# drvamap.net
KiCad netlist of a schematic drawn in Altium Designer
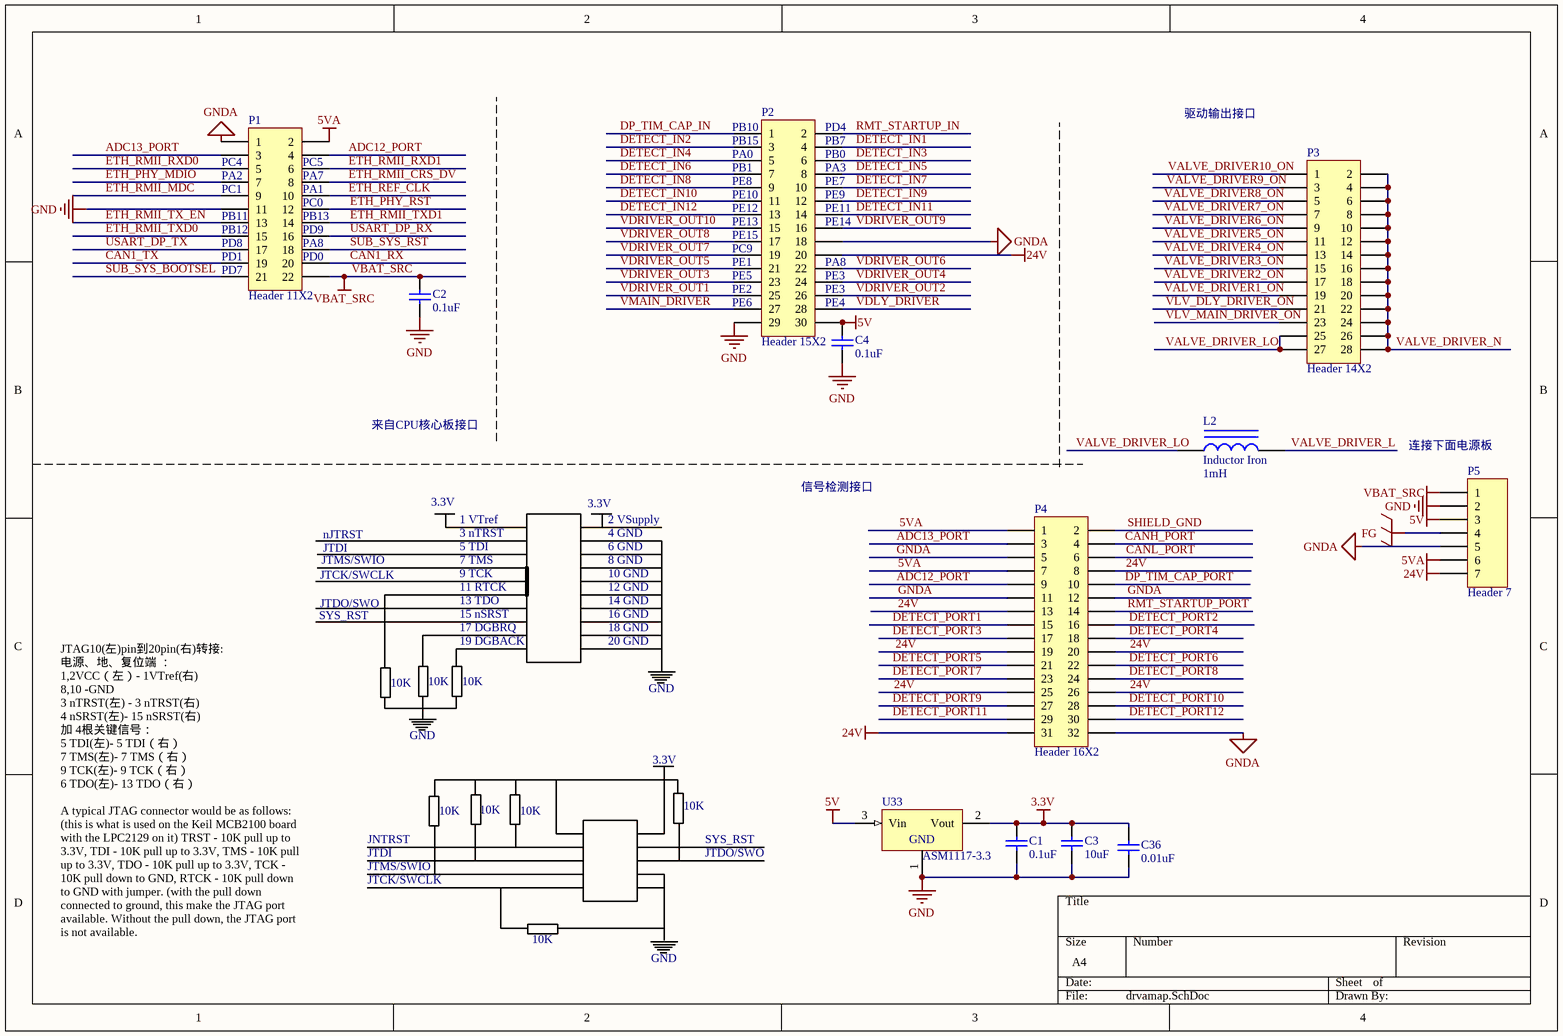
[diagram p0: drvamap.SchDoc]

(export (version "E")
  (design (tool "Eeschema 10.0.6"))
  (components
    (comp (ref "C1")
      (value "0.1uF")
      (footprint "CAPC2012M")
      (description "Capacitor")
      (fields (field (name "PUBLISHER") "Altium Limited"))
      (libsource (lib "Miscellaneous Devices") (part "Cap"))
    )
    (comp (ref "C2")
      (value "0.1uF")
      (footprint "CAPC2012M")
      (description "Capacitor")
      (fields (field (name "PUBLISHER") "Altium Limited"))
      (libsource (lib "Miscellaneous Devices") (part "Cap"))
    )
    (comp (ref "C3")
      (value "10uF")
      (footprint "CAPC2012M")
      (description "Capacitor")
      (fields (field (name "PUBLISHER") "Altium Limited"))
      (libsource (lib "Miscellaneous Devices") (part "Cap"))
    )
    (comp (ref "C4")
      (value "0.1uF")
      (footprint "CAPC2012M")
      (description "Capacitor")
      (fields (field (name "PUBLISHER") "Altium Limited"))
      (libsource (lib "Miscellaneous Devices") (part "Cap"))
    )
    (comp (ref "C36")
      (value "0.01uF")
      (footprint "CAPC2012M")
      (description "Capacitor")
      (fields (field (name "PUBLISHER") "Altium Limited"))
      (libsource (lib "Miscellaneous Devices") (part "Cap"))
    )
    (comp (ref "L2")
      (value "Inductor Iron")
      (footprint "CAPPR5-8x8A")
      (description "Magnetic-Core Inductor")
      (fields (field (name "ALTIUM_VALUE") "1mH") (field (name "PUBLISHER") "Altium Limited"))
      (libsource (lib "Miscellaneous Devices") (part "Inductor Iron"))
    )
    (comp (ref "P1")
      (value "Header 11X2")
      (footprint "HDR2X11")
      (description "Header, 11-Pin, Dual row")
      (fields (field (name "PUBLISHER") "Altium Limited"))
      (libsource (lib "UserSchCon") (part "Header 11X2"))
    )
    (comp (ref "P2")
      (value "Header 15X2")
      (footprint "HDR2X15")
      (description "Header, 15-Pin, Dual row")
      (fields (field (name "PUBLISHER") "Altium Limited"))
      (libsource (lib "UserSchCon") (part "Header 15X2"))
    )
    (comp (ref "P3")
      (value "Header 14X2")
      (footprint "DG127A-3.81-14")
      (description "Header, 14-Pin, Dual row")
      (fields (field (name "PUBLISHER") "Altium Limited"))
      (libsource (lib "UserSchCon") (part "Header 14X2"))
    )
    (comp (ref "P4")
      (value "Header 16X2")
      (footprint "DG127A-3.81-16")
      (description "Header, 16-Pin, Dual row")
      (fields (field (name "PUBLISHER") "Altium Limited"))
      (libsource (lib "UserSchCon") (part "Header 16X2"))
    )
    (comp (ref "P5")
      (value "Header 7")
      (footprint "HDR1X7")
      (description "Header, 7-Pin")
      (fields (field (name "PUBLISHER") "Altium Limited"))
      (libsource (lib "UserSchCon") (part "Header 7"))
    )
    (comp (ref "U33")
      (value "ASM1117-3.3")
      (footprint "SOT-223")
      (description "800mA Low-Dropout Linear Regulator")
      (libsource (lib "UserLib") (part "LM1117T-5.0"))
    )
  )
  (nets
    (net (code "1") (name "/ADC12_PORT") (class "Default")
      (node (ref "P1") (pin "4") (pinfunction "4_4") (pintype "passive"))
      (node (ref "P4") (pin "9") (pinfunction "9_9") (pintype "passive"))
    )
    (net (code "2") (name "/ADC13_PORT") (class "Default")
      (node (ref "P1") (pin "3") (pinfunction "3_3") (pintype "passive"))
      (node (ref "P4") (pin "3") (pinfunction "3_3") (pintype "passive"))
    )
    (net (code "3") (name "/CAN1_RX") (class "Default")
      (node (ref "P1") (pin "20") (pinfunction "20_20") (pintype "passive"))
    )
    (net (code "4") (name "/CAN1_TX") (class "Default")
      (node (ref "P1") (pin "19") (pinfunction "19_19") (pintype "passive"))
    )
    (net (code "5") (name "/CANH_PORT") (class "Default")
      (node (ref "P4") (pin "4") (pinfunction "4_4") (pintype "passive"))
    )
    (net (code "6") (name "/CANL_PORT") (class "Default")
      (node (ref "P4") (pin "6") (pinfunction "6_6") (pintype "passive"))
    )
    (net (code "7") (name "/DETECT_IN1") (class "Default")
      (node (ref "P2") (pin "4") (pinfunction "4_4") (pintype "passive"))
    )
    (net (code "8") (name "/DETECT_IN2") (class "Default")
      (node (ref "P2") (pin "3") (pinfunction "3_3") (pintype "passive"))
    )
    (net (code "9") (name "/DETECT_IN3") (class "Default")
      (node (ref "P2") (pin "6") (pinfunction "6_6") (pintype "passive"))
    )
    (net (code "10") (name "/DETECT_IN4") (class "Default")
      (node (ref "P2") (pin "5") (pinfunction "5_5") (pintype "passive"))
    )
    (net (code "11") (name "/DETECT_IN5") (class "Default")
      (node (ref "P2") (pin "8") (pinfunction "8_8") (pintype "passive"))
    )
    (net (code "12") (name "/DETECT_IN6") (class "Default")
      (node (ref "P2") (pin "7") (pinfunction "7_7") (pintype "passive"))
    )
    (net (code "13") (name "/DETECT_IN7") (class "Default")
      (node (ref "P2") (pin "10") (pinfunction "10_10") (pintype "passive"))
    )
    (net (code "14") (name "/DETECT_IN8") (class "Default")
      (node (ref "P2") (pin "9") (pinfunction "9_9") (pintype "passive"))
    )
    (net (code "15") (name "/DETECT_IN9") (class "Default")
      (node (ref "P2") (pin "12") (pinfunction "12_12") (pintype "passive"))
    )
    (net (code "16") (name "/DETECT_IN10") (class "Default")
      (node (ref "P2") (pin "11") (pinfunction "11_11") (pintype "passive"))
    )
    (net (code "17") (name "/DETECT_IN11") (class "Default")
      (node (ref "P2") (pin "14") (pinfunction "14_14") (pintype "passive"))
    )
    (net (code "18") (name "/DETECT_IN12") (class "Default")
      (node (ref "P2") (pin "13") (pinfunction "13_13") (pintype "passive"))
    )
    (net (code "19") (name "/DETECT_PORT1") (class "Default")
      (node (ref "P4") (pin "15") (pinfunction "15_15") (pintype "passive"))
    )
    (net (code "20") (name "/DETECT_PORT2") (class "Default")
      (node (ref "P4") (pin "16") (pinfunction "16_16") (pintype "passive"))
    )
    (net (code "21") (name "/DETECT_PORT3") (class "Default")
      (node (ref "P4") (pin "17") (pinfunction "17_17") (pintype "passive"))
    )
    (net (code "22") (name "/DETECT_PORT4") (class "Default")
      (node (ref "P4") (pin "18") (pinfunction "18_18") (pintype "passive"))
    )
    (net (code "23") (name "/DETECT_PORT5") (class "Default")
      (node (ref "P4") (pin "21") (pinfunction "21_21") (pintype "passive"))
    )
    (net (code "24") (name "/DETECT_PORT6") (class "Default")
      (node (ref "P4") (pin "22") (pinfunction "22_22") (pintype "passive"))
    )
    (net (code "25") (name "/DETECT_PORT7") (class "Default")
      (node (ref "P4") (pin "23") (pinfunction "23_23") (pintype "passive"))
    )
    (net (code "26") (name "/DETECT_PORT8") (class "Default")
      (node (ref "P4") (pin "24") (pinfunction "24_24") (pintype "passive"))
    )
    (net (code "27") (name "/DETECT_PORT9") (class "Default")
      (node (ref "P4") (pin "27") (pinfunction "27_27") (pintype "passive"))
    )
    (net (code "28") (name "/DETECT_PORT10") (class "Default")
      (node (ref "P4") (pin "28") (pinfunction "28_28") (pintype "passive"))
    )
    (net (code "29") (name "/DETECT_PORT11") (class "Default")
      (node (ref "P4") (pin "29") (pinfunction "29_29") (pintype "passive"))
    )
    (net (code "30") (name "/DETECT_PORT12") (class "Default")
      (node (ref "P4") (pin "30") (pinfunction "30_30") (pintype "passive"))
    )
    (net (code "31") (name "/DP_TIM_CAP_IN") (class "Default")
      (node (ref "P2") (pin "1") (pinfunction "1_1") (pintype "passive"))
    )
    (net (code "32") (name "/DP_TIM_CAP_PORT") (class "Default")
      (node (ref "P4") (pin "10") (pinfunction "10_10") (pintype "passive"))
    )
    (net (code "33") (name "/ETH_PHY_MDIO") (class "Default")
      (node (ref "P1") (pin "7") (pinfunction "7_7") (pintype "passive"))
    )
    (net (code "34") (name "/ETH_PHY_RST") (class "Default")
      (node (ref "P1") (pin "12") (pinfunction "12_12") (pintype "passive"))
    )
    (net (code "35") (name "/ETH_REF_CLK") (class "Default")
      (node (ref "P1") (pin "10") (pinfunction "10_10") (pintype "passive"))
    )
    (net (code "36") (name "/ETH_RMII_CRS_DV") (class "Default")
      (node (ref "P1") (pin "8") (pinfunction "8_8") (pintype "passive"))
    )
    (net (code "37") (name "/ETH_RMII_MDC") (class "Default")
      (node (ref "P1") (pin "9") (pinfunction "9_9") (pintype "passive"))
    )
    (net (code "38") (name "/ETH_RMII_RXD0") (class "Default")
      (node (ref "P1") (pin "5") (pinfunction "5_5") (pintype "passive"))
    )
    (net (code "39") (name "/ETH_RMII_RXD1") (class "Default")
      (node (ref "P1") (pin "6") (pinfunction "6_6") (pintype "passive"))
    )
    (net (code "40") (name "/ETH_RMII_TXD0") (class "Default")
      (node (ref "P1") (pin "15") (pinfunction "15_15") (pintype "passive"))
    )
    (net (code "41") (name "/ETH_RMII_TXD1") (class "Default")
      (node (ref "P1") (pin "14") (pinfunction "14_14") (pintype "passive"))
    )
    (net (code "42") (name "/ETH_RMII_TX_EN") (class "Default")
      (node (ref "P1") (pin "13") (pinfunction "13_13") (pintype "passive"))
    )
    (net (code "43") (name "/RMT_STARTUP_IN") (class "Default")
      (node (ref "P2") (pin "2") (pinfunction "2_2") (pintype "passive"))
    )
    (net (code "44") (name "/RMT_STARTUP_PORT") (class "Default")
      (node (ref "P4") (pin "14") (pinfunction "14_14") (pintype "passive"))
    )
    (net (code "45") (name "/SHIELD_GND") (class "Default")
      (node (ref "P4") (pin "2") (pinfunction "2_2") (pintype "passive"))
    )
    (net (code "46") (name "/SUB_SYS_BOOTSEL") (class "Default")
      (node (ref "P1") (pin "21") (pinfunction "21_21") (pintype "passive"))
    )
    (net (code "47") (name "/SUB_SYS_RST") (class "Default")
      (node (ref "P1") (pin "18") (pinfunction "18_18") (pintype "passive"))
    )
    (net (code "48") (name "/USART_DP_RX") (class "Default")
      (node (ref "P1") (pin "16") (pinfunction "16_16") (pintype "passive"))
    )
    (net (code "49") (name "/USART_DP_TX") (class "Default")
      (node (ref "P1") (pin "17") (pinfunction "17_17") (pintype "passive"))
    )
    (net (code "50") (name "/VALVE_DRIVER1_ON") (class "Default")
      (node (ref "P3") (pin "19") (pinfunction "19_19") (pintype "passive"))
    )
    (net (code "51") (name "/VALVE_DRIVER2_ON") (class "Default")
      (node (ref "P3") (pin "17") (pinfunction "17_17") (pintype "passive"))
    )
    (net (code "52") (name "/VALVE_DRIVER3_ON") (class "Default")
      (node (ref "P3") (pin "15") (pinfunction "15_15") (pintype "passive"))
    )
    (net (code "53") (name "/VALVE_DRIVER4_ON") (class "Default")
      (node (ref "P3") (pin "13") (pinfunction "13_13") (pintype "passive"))
    )
    (net (code "54") (name "/VALVE_DRIVER5_ON") (class "Default")
      (node (ref "P3") (pin "11") (pinfunction "11_11") (pintype "passive"))
    )
    (net (code "55") (name "/VALVE_DRIVER6_ON") (class "Default")
      (node (ref "P3") (pin "9") (pinfunction "9_9") (pintype "passive"))
    )
    (net (code "56") (name "/VALVE_DRIVER7_ON") (class "Default")
      (node (ref "P3") (pin "7") (pinfunction "7_7") (pintype "passive"))
    )
    (net (code "57") (name "/VALVE_DRIVER8_ON") (class "Default")
      (node (ref "P3") (pin "5") (pinfunction "5_5") (pintype "passive"))
    )
    (net (code "58") (name "/VALVE_DRIVER9_ON") (class "Default")
      (node (ref "P3") (pin "3") (pinfunction "3_3") (pintype "passive"))
    )
    (net (code "59") (name "/VALVE_DRIVER10_ON") (class "Default")
      (node (ref "P3") (pin "1") (pinfunction "1_1") (pintype "passive"))
    )
    (net (code "60") (name "/VALVE_DRIVER_L") (class "Default")
      (node (ref "L2") (pin "2") (pinfunction "2_2") (pintype "passive"))
    )
    (net (code "61") (name "/VALVE_DRIVER_LO") (class "Default")
      (node (ref "L2") (pin "1") (pinfunction "1_1") (pintype "passive"))
      (node (ref "P3") (pin "25") (pinfunction "25_25") (pintype "passive"))
      (node (ref "P3") (pin "27") (pinfunction "27_27") (pintype "passive"))
    )
    (net (code "62") (name "/VALVE_DRIVER_N") (class "Default")
      (node (ref "P3") (pin "10") (pinfunction "10_10") (pintype "passive"))
      (node (ref "P3") (pin "12") (pinfunction "12_12") (pintype "passive"))
      (node (ref "P3") (pin "14") (pinfunction "14_14") (pintype "passive"))
      (node (ref "P3") (pin "16") (pinfunction "16_16") (pintype "passive"))
      (node (ref "P3") (pin "18") (pinfunction "18_18") (pintype "passive"))
      (node (ref "P3") (pin "2") (pinfunction "2_2") (pintype "passive"))
      (node (ref "P3") (pin "20") (pinfunction "20_20") (pintype "passive"))
      (node (ref "P3") (pin "22") (pinfunction "22_22") (pintype "passive"))
      (node (ref "P3") (pin "24") (pinfunction "24_24") (pintype "passive"))
      (node (ref "P3") (pin "26") (pinfunction "26_26") (pintype "passive"))
      (node (ref "P3") (pin "28") (pinfunction "28_28") (pintype "passive"))
      (node (ref "P3") (pin "4") (pinfunction "4_4") (pintype "passive"))
      (node (ref "P3") (pin "6") (pinfunction "6_6") (pintype "passive"))
      (node (ref "P3") (pin "8") (pinfunction "8_8") (pintype "passive"))
    )
    (net (code "63") (name "/VDLY_DRIVER") (class "Default")
      (node (ref "P2") (pin "28") (pinfunction "28_28") (pintype "passive"))
    )
    (net (code "64") (name "/VDRIVER_OUT1") (class "Default")
      (node (ref "P2") (pin "25") (pinfunction "25_25") (pintype "passive"))
    )
    (net (code "65") (name "/VDRIVER_OUT2") (class "Default")
      (node (ref "P2") (pin "26") (pinfunction "26_26") (pintype "passive"))
    )
    (net (code "66") (name "/VDRIVER_OUT3") (class "Default")
      (node (ref "P2") (pin "23") (pinfunction "23_23") (pintype "passive"))
    )
    (net (code "67") (name "/VDRIVER_OUT4") (class "Default")
      (node (ref "P2") (pin "24") (pinfunction "24_24") (pintype "passive"))
    )
    (net (code "68") (name "/VDRIVER_OUT5") (class "Default")
      (node (ref "P2") (pin "21") (pinfunction "21_21") (pintype "passive"))
    )
    (net (code "69") (name "/VDRIVER_OUT6") (class "Default")
      (node (ref "P2") (pin "22") (pinfunction "22_22") (pintype "passive"))
    )
    (net (code "70") (name "/VDRIVER_OUT7") (class "Default")
      (node (ref "P2") (pin "19") (pinfunction "19_19") (pintype "passive"))
    )
    (net (code "71") (name "/VDRIVER_OUT8") (class "Default")
      (node (ref "P2") (pin "17") (pinfunction "17_17") (pintype "passive"))
    )
    (net (code "72") (name "/VDRIVER_OUT9") (class "Default")
      (node (ref "P2") (pin "16") (pinfunction "16_16") (pintype "passive"))
    )
    (net (code "73") (name "/VDRIVER_OUT10") (class "Default")
      (node (ref "P2") (pin "15") (pinfunction "15_15") (pintype "passive"))
    )
    (net (code "74") (name "/VLV_DLY_DRIVER_ON") (class "Default")
      (node (ref "P3") (pin "21") (pinfunction "21_21") (pintype "passive"))
    )
    (net (code "75") (name "/VLV_MAIN_DRIVER_ON") (class "Default")
      (node (ref "P3") (pin "23") (pinfunction "23_23") (pintype "passive"))
    )
    (net (code "76") (name "/VMAIN_DRIVER") (class "Default")
      (node (ref "P2") (pin "27") (pinfunction "27_27") (pintype "passive"))
    )
    (net (code "77") (name "3.3V") (class "Default")
      (node (ref "C1") (pin "2") (pinfunction "2_2") (pintype "passive"))
      (node (ref "C3") (pin "2") (pinfunction "2_2") (pintype "passive"))
      (node (ref "C36") (pin "2") (pinfunction "2_2") (pintype "passive"))
      (node (ref "U33") (pin "2") (pinfunction "Vout_2") (pintype "power_in"))
    )
    (net (code "78") (name "5V") (class "Default")
      (node (ref "C4") (pin "1") (pinfunction "1_1") (pintype "passive"))
      (node (ref "P2") (pin "30") (pinfunction "30_30") (pintype "passive"))
      (node (ref "P5") (pin "3") (pinfunction "3_3") (pintype "passive"))
      (node (ref "U33") (pin "3") (pinfunction "Vin_3") (pintype "input"))
    )
    (net (code "79") (name "5VA") (class "Default")
      (node (ref "P1") (pin "2") (pinfunction "2_2") (pintype "passive"))
      (node (ref "P4") (pin "1") (pinfunction "1_1") (pintype "passive"))
      (node (ref "P4") (pin "7") (pinfunction "7_7") (pintype "passive"))
      (node (ref "P5") (pin "6") (pinfunction "6_6") (pintype "passive"))
    )
    (net (code "80") (name "24V") (class "Default")
      (node (ref "P2") (pin "20") (pinfunction "20_20") (pintype "passive"))
      (node (ref "P4") (pin "13") (pinfunction "13_13") (pintype "passive"))
      (node (ref "P4") (pin "19") (pinfunction "19_19") (pintype "passive"))
      (node (ref "P4") (pin "20") (pinfunction "20_20") (pintype "passive"))
      (node (ref "P4") (pin "25") (pinfunction "25_25") (pintype "passive"))
      (node (ref "P4") (pin "26") (pinfunction "26_26") (pintype "passive"))
      (node (ref "P4") (pin "31") (pinfunction "31_31") (pintype "passive"))
      (node (ref "P4") (pin "8") (pinfunction "8_8") (pintype "passive"))
      (node (ref "P5") (pin "7") (pinfunction "7_7") (pintype "passive"))
    )
    (net (code "81") (name "FG") (class "Default")
      (node (ref "P5") (pin "4") (pinfunction "4_4") (pintype "passive"))
    )
    (net (code "82") (name "GND") (class "Default")
      (node (ref "C1") (pin "1") (pinfunction "1_1") (pintype "passive"))
      (node (ref "C2") (pin "2") (pinfunction "2_2") (pintype "passive"))
      (node (ref "C3") (pin "1") (pinfunction "1_1") (pintype "passive"))
      (node (ref "C36") (pin "1") (pinfunction "1_1") (pintype "passive"))
      (node (ref "C4") (pin "2") (pinfunction "2_2") (pintype "passive"))
      (node (ref "P1") (pin "11") (pinfunction "11_11") (pintype "passive"))
      (node (ref "P2") (pin "29") (pinfunction "29_29") (pintype "passive"))
      (node (ref "P5") (pin "2") (pinfunction "2_2") (pintype "passive"))
      (node (ref "U33") (pin "1") (pinfunction "GND_1") (pintype "passive"))
    )
    (net (code "83") (name "GNDA") (class "Default")
      (node (ref "P1") (pin "1") (pinfunction "1_1") (pintype "passive"))
      (node (ref "P2") (pin "18") (pinfunction "18_18") (pintype "passive"))
      (node (ref "P4") (pin "11") (pinfunction "11_11") (pintype "passive"))
      (node (ref "P4") (pin "12") (pinfunction "12_12") (pintype "passive"))
      (node (ref "P4") (pin "32") (pinfunction "32_32") (pintype "passive"))
      (node (ref "P4") (pin "5") (pinfunction "5_5") (pintype "passive"))
      (node (ref "P5") (pin "5") (pinfunction "5_5") (pintype "passive"))
    )
    (net (code "84") (name "VBAT_SRC") (class "Default")
      (node (ref "C2") (pin "1") (pinfunction "1_1") (pintype "passive"))
      (node (ref "P1") (pin "22") (pinfunction "22_22") (pintype "passive"))
      (node (ref "P5") (pin "1") (pinfunction "1_1") (pintype "passive"))
    )
  )
)
